# Xds100v2Emu.net
KiCad netlist of a schematic drawn in Altium Designer
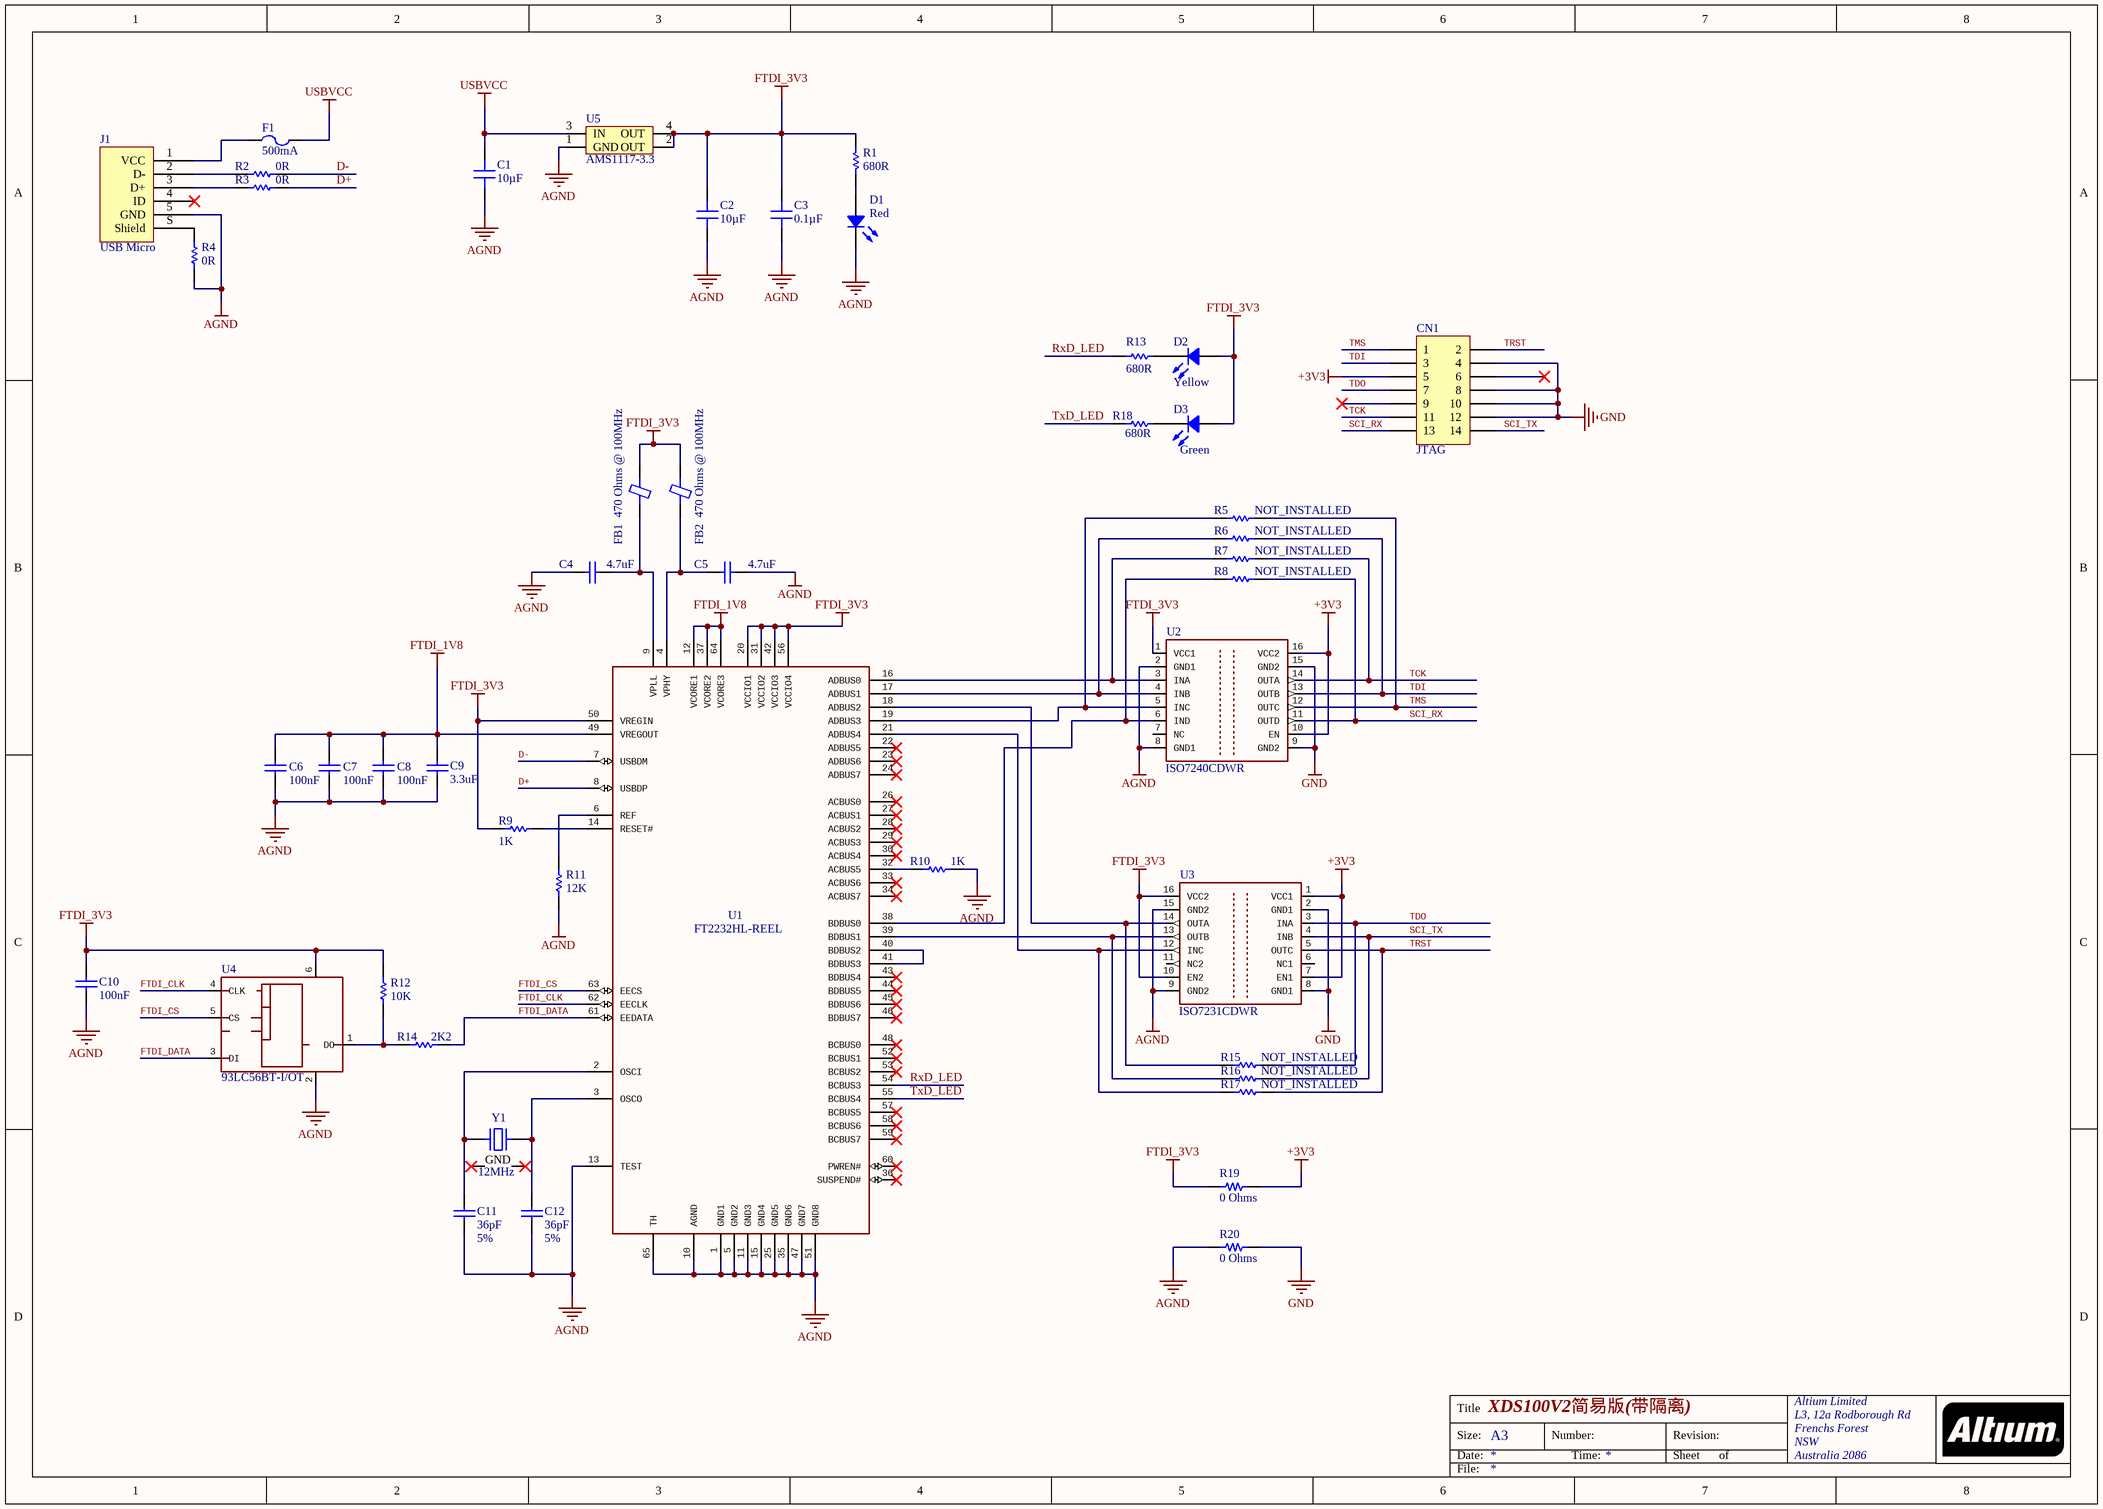
[diagram p0: Xds100v2Emu.SchDoc]

(export (version "E")
  (design (tool "Eeschema 10.0.6"))
  (components
    (comp (ref "C1")
      (value "10µF")
      (footprint "CAP 0805_2012")
      (description "CAP CER 10UF 16V X7R 0805")
      (fields
        (field (name "PART NUMBER") "CL21B106KOQNNNG")
        (field (name "MANUFACTURER") "Samsung Electro-Mechanics")
      )
      (libsource (lib "Altium Database Library V2") (part "Capacitor"))
    )
    (comp (ref "C2")
      (value "10µF")
      (footprint "CAP 0805_2012")
      (description "CAP CER 10UF 16V X7R 0805")
      (fields
        (field (name "PART NUMBER") "CL21B106KOQNNNG")
        (field (name "MANUFACTURER") "Samsung Electro-Mechanics")
      )
      (libsource (lib "Altium Database Library V2") (part "Capacitor"))
    )
    (comp (ref "C3")
      (value "0.1µF")
      (footprint "CAP 0603_1608")
      (description "CAP CER 0.1UF 16V X7R 0603")
      (fields
        (field (name "PART NUMBER") "GCJ188R71C104KA01D")
        (field (name "MANUFACTURER") "Murata Electronics")
      )
      (libsource (lib "Altium Database Library V2") (part "Capacitor"))
    )
    (comp (ref "C4")
      (value "4.7uF")
      (footprint "CAP 0603/1608")
      (description "CAP,4.7UF,+/-20%,X5R,6.3V,SMD0603")
      (fields
        (field (name "MANUFACTURER") "KEMET")
        (field (name "MANUFACTURER PART NUMBER") "C0603C475M8PACTU")
      )
      (libsource (lib "Embest") (part "C"))
    )
    (comp (ref "C5")
      (value "4.7uF")
      (footprint "CAP 0603/1608")
      (description "CAP,4.7UF,+/-20%,X5R,6.3V,SMD0603")
      (fields
        (field (name "MANUFACTURER") "KEMET")
        (field (name "MANUFACTURER PART NUMBER") "C0603C475M8PACTU")
      )
      (libsource (lib "Embest") (part "C"))
    )
    (comp (ref "C6")
      (value "100nF")
      (footprint "CAP 0603/1608")
      (description "CAP,100NF(0.1uf),+/-10%,X5R,16V,SMD0603")
      (libsource (lib "Embest") (part "C"))
    )
    (comp (ref "C7")
      (value "100nF")
      (footprint "CAP 0603/1608")
      (description "CAP,100NF(0.1uf),+/-10%,X5R,16V,SMD0603")
      (libsource (lib "Embest") (part "C"))
    )
    (comp (ref "C8")
      (value "100nF")
      (footprint "CAP 0603/1608")
      (description "CAP,100NF(0.1uf),+/-10%,X5R,16V,SMD0603")
      (libsource (lib "Embest") (part "C"))
    )
    (comp (ref "C9")
      (value "3.3uF")
      (footprint "CAP 0603/1608")
      (description "CAP,3.3uF,+/-10%,X5R,10V,SMD0603")
      (fields
        (field (name "MANUFACTURER") "MURATA")
        (field (name "MANUFACTURER PART NUMBER") "GRM188R61A335KE15D")
      )
      (libsource (lib "Embest") (part "C"))
    )
    (comp (ref "C10")
      (value "100nF")
      (footprint "CAP 0603/1608")
      (description "CAP,100NF(0.1uf),+/-10%,X5R,10V,SMD0603")
      (fields
        (field (name "MANUFACTURER") "MURATA")
        (field (name "MANUFACTURER PART NUMBER") "GRM155R61A104KA01D")
      )
      (libsource (lib "Embest") (part "C"))
    )
    (comp (ref "C11")
      (value "36pF")
      (footprint "CAP 0603/1608")
      (description "CAP,36pF,+/-5%,C0G,50V,SMD0603")
      (fields
        (field (name "RATING") "5%")
        (field (name "MANUFACTURER") "MURATA")
        (field (name "MANUFACTURER PART NUMBER") "GRM1555C1H360JA01D")
      )
      (libsource (lib "Embest") (part "C"))
    )
    (comp (ref "C12")
      (value "36pF")
      (footprint "CAP 0603/1608")
      (description "CAP,36pF,+/-5%,C0G,50V,SMD0603")
      (fields
        (field (name "RATING") "5%")
        (field (name "MANUFACTURER") "MURATA")
        (field (name "MANUFACTURER PART NUMBER") "GRM1555C1H360JA01D")
      )
      (libsource (lib "Embest") (part "C"))
    )
    (comp (ref "CN1")
      (value "JTAG")
      (footprint "JTAG调试接口")
      (description "Header, 14-Pin")
      (libsource (lib "Miscellaneous Connectors") (part "Header 7X2"))
    )
    (comp (ref "D1")
      (value "Red")
      (footprint "LED 0603_1608 RED")
      (description "LED RED CLEAR 0603 SMD")
      (fields
        (field (name "PART NUMBER") "SML-LXFM0603SIC-TR")
        (field (name "MANUFACTURER") "Lumex Opto/Components Inc.")
      )
      (libsource (lib "Altium Database Library V2") (part "LED"))
    )
    (comp (ref "D2")
      (value "Yellow")
      (footprint "LED 0603_1608 YELLOW")
      (description "LED YELLOW DIFFUSED 0603 SMD")
      (fields (field (name "PART NUMBER") "SML-D12Y8WT86") (field (name "MANUFACTURER") "Rohm Semiconductor"))
      (libsource (lib "Altium Database Library V2") (part "LED"))
    )
    (comp (ref "D3")
      (value "Green")
      (footprint "LED 0603_1608 GREEN")
      (description "LED GREEN DIFFUSED 0603 SMD")
      (fields (field (name "PART NUMBER") "SML-D13FWT86") (field (name "MANUFACTURER") "Rohm Semiconductor"))
      (libsource (lib "Altium Database Library V2") (part "LED"))
    )
    (comp (ref "F1")
      (value "500mA")
      (footprint "FUSM4632X85N")
      (description "PTC RESETTABLE .50A 15V 1812")
      (fields (field (name "MANUFACTURER") "BOURNS") (field (name "MANUFACTURER PART NUMBER") "MF-MSMF050-2"))
      (libsource (lib "Embest") (part "F"))
    )
    (comp (ref "FB1")
      (value "470 Ohms @ 100MHz")
      (footprint "FER 0603_1608")
      (description "FERRITE BEAD 470 OHM 0603 1LN")
      (fields
        (field (name "PART NUMBER") "BLM18BB471SN1D")
        (field (name "MANUFACTURER") "Murata Electronics")
      )
      (libsource (lib "Altium Database Library V2") (part "Ferrite Chip"))
    )
    (comp (ref "FB2")
      (value "470 Ohms @ 100MHz")
      (footprint "FER 0603_1608")
      (description "FERRITE BEAD 470 OHM 0603 1LN")
      (fields
        (field (name "PART NUMBER") "BLM18BB471SN1D")
        (field (name "MANUFACTURER") "Murata Electronics")
      )
      (libsource (lib "Altium Database Library V2") (part "Ferrite Chip"))
    )
    (comp (ref "J1")
      (value "USB Micro")
      (footprint "FCI USB 10118193-0001LF")
      (libsource (lib "Connectors") (part "USB 2.0 Type B Micro"))
    )
    (comp (ref "R1")
      (value "680R")
      (footprint "RES 0603/1608")
      (description "RES,680R,+/-5%,1/10W,SMD0603")
      (libsource (lib "Embest") (part "R"))
    )
    (comp (ref "R2")
      (value "0R")
      (footprint "RES 0603/1608")
      (description "RES,0R,+/-5%,1/10W,SMD0603")
      (libsource (lib "Embest") (part "R"))
    )
    (comp (ref "R3")
      (value "0R")
      (footprint "RES 0603/1608")
      (description "RES,0R,+/-5%,1/10W,SMD0603")
      (libsource (lib "Embest") (part "R"))
    )
    (comp (ref "R4")
      (value "0R")
      (footprint "RES 0603/1608")
      (description "RES,0R,+/-5%,1/10W,SMD0603")
      (libsource (lib "Embest") (part "R"))
    )
    (comp (ref "R5")
      (value "NOT_INSTALLED")
      (footprint "RES 0603/1608")
      (description "RES,0R,+/-5%,1/10W,SMD0603")
      (libsource (lib "Embest") (part "R"))
    )
    (comp (ref "R6")
      (value "NOT_INSTALLED")
      (footprint "RES 0603/1608")
      (description "RES,0R,+/-5%,1/10W,SMD0603")
      (libsource (lib "Embest") (part "R"))
    )
    (comp (ref "R7")
      (value "NOT_INSTALLED")
      (footprint "RES 0603/1608")
      (description "RES,0R,+/-5%,1/10W,SMD0603")
      (libsource (lib "Embest") (part "R"))
    )
    (comp (ref "R8")
      (value "NOT_INSTALLED")
      (footprint "RES 0603/1608")
      (description "RES,0R,+/-5%,1/10W,SMD0603")
      (libsource (lib "Embest") (part "R"))
    )
    (comp (ref "R9")
      (value "1K")
      (footprint "RES 0603/1608")
      (description "RES,1K,+/-5%,1/10W,SMD0603")
      (libsource (lib "Embest") (part "R"))
    )
    (comp (ref "R10")
      (value "1K")
      (footprint "RES 0603/1608")
      (description "RES,1K,+/-1%,1/10W,SMD0603")
      (libsource (lib "Embest") (part "R"))
    )
    (comp (ref "R11")
      (value "12K")
      (footprint "RES 0603/1608")
      (description "RES,12K,+/-1%,1/10W,SMD0603")
      (libsource (lib "Embest") (part "R"))
    )
    (comp (ref "R12")
      (value "10K")
      (footprint "RES 0603/1608")
      (description "RES,10K,+/-1%,1/10W,SMD0603")
      (libsource (lib "Embest") (part "R"))
    )
    (comp (ref "R13")
      (value "680R")
      (footprint "RES 0603/1608")
      (description "RES,680R,+/-5%,1/10W,SMD0603")
      (libsource (lib "Embest") (part "R"))
    )
    (comp (ref "R14")
      (value "2K2")
      (footprint "RES 0603/1608")
      (description "RES,2K2,+/-1%,1/10W,SMD0603")
      (libsource (lib "Embest") (part "R"))
    )
    (comp (ref "R15")
      (value "NOT_INSTALLED")
      (footprint "RES 0603/1608")
      (description "RES,0R,+/-5%,1/10W,SMD0603")
      (libsource (lib "Embest") (part "R"))
    )
    (comp (ref "R16")
      (value "NOT_INSTALLED")
      (footprint "RES 0603/1608")
      (description "RES,0R,+/-5%,1/10W,SMD0603")
      (libsource (lib "Embest") (part "R"))
    )
    (comp (ref "R17")
      (value "NOT_INSTALLED")
      (footprint "RES 0603/1608")
      (description "RES,0R,+/-5%,1/10W,SMD0603")
      (libsource (lib "Embest") (part "R"))
    )
    (comp (ref "R18")
      (value "680R")
      (footprint "RES 0603/1608")
      (description "RES,680R,+/-1%,1/10W,SMD0603")
      (libsource (lib "Embest") (part "R"))
    )
    (comp (ref "R19")
      (value "0 Ohms")
      (footprint "RES 0603_1608")
      (description "RES 0 OHM JUMPER 1/10W 0603")
      (fields (field (name "PART NUMBER") "SFR03EZPJ000") (field (name "MANUFACTURER") "Rohm Semiconductor"))
      (libsource (lib "Altium Database Library V2") (part "Resistor"))
    )
    (comp (ref "R20")
      (value "0 Ohms")
      (footprint "RES 0603_1608")
      (description "RES 0 OHM JUMPER 1/10W 0603")
      (fields (field (name "PART NUMBER") "SFR03EZPJ000") (field (name "MANUFACTURER") "Rohm Semiconductor"))
      (libsource (lib "Altium Database Library V2") (part "Resistor"))
    )
    (comp (ref "U1")
      (value "FT2232HL-REEL")
      (footprint "LQFP64_N")
      (description "IC,Dual High Speed USB to Multipurpose UART/FIFO IC,FT2232HL-REEL,LQFP-64,SMD")
      (fields (field (name "MANUFACTURER") "FTDI") (field (name "Comment") "FT2232HQ-REEL"))
      (libsource (lib "Embest") (part "FT2232HQ"))
    )
    (comp (ref "U2")
      (value "ISO7240CDWR")
      (footprint "SOIC127P1030X265-16N")
      (description "IC DGTL ISO 4CH CMOS 16SOIC,CUSTOMER SUPPLY")
      (fields (field (name "MANUFACTURER") "TI"))
      (libsource (lib "Embest") (part "ISO7240"))
    )
    (comp (ref "U3")
      (value "ISO7231CDWR")
      (footprint "SOIC127P1030X265-16N")
      (description "IC DGTL ISO 3CH CMOS 16SOIC,CUSTOMER SUPPLY")
      (fields (field (name "MANUFACTURER") "TI"))
      (libsource (lib "Embest") (part "ISO7231"))
    )
    (comp (ref "U4")
      (value "93LC56BT-I/OT")
      (footprint "SOT23-6")
      (description "IC,EEPROM Serial-Microwire 2K-Bit 128 x 16 2MHz,93LC56BT-I/OT,SOT-23-6,SMD")
      (fields (field (name "MANUFACTURER") "MICROCHIP"))
      (libsource (lib "Embest") (part "93LC56BT"))
    )
    (comp (ref "U5")
      (value "AMS1117-3.3")
      (footprint "PCB - LEADED - SOT - DIODES SOT-223:DIODES SOT-223")
      (description "电源转换5Vto3.3V")
      (libsource (lib "IC") (part "AMS1117"))
    )
    (comp (ref "Y1")
      (value "12MHz")
      (footprint "NDK NX3225SA")
      (description "CRYSTAL 12.0000MHZ 8PF SMD")
      (fields
        (field (name "PART NUMBER") "NX3225SA-12MHZ-STD-CSR-6")
        (field (name "MANUFACTURER") "NDK America, Inc.")
      )
      (libsource (lib "Altium Database Library V2") (part "NDK Crystal NX3225SA"))
    )
  )
  (nets
    (net (code "1") (name "+3V3") (class "Default")
      (node (ref "CN1") (pin "5") (pinfunction "5_5") (pintype "passive"))
      (node (ref "R19") (pin "2") (pinfunction "2_2") (pintype "passive"))
      (node (ref "U2") (pin "10") (pinfunction "EN_10") (pintype "passive"))
      (node (ref "U2") (pin "16") (pinfunction "VCC2_16") (pintype "power_in"))
      (node (ref "U3") (pin "1") (pinfunction "VCC1_1") (pintype "power_in"))
      (node (ref "U3") (pin "7") (pinfunction "EN1_7") (pintype "passive"))
    )
    (net (code "2") (name "/D+") (class "Default")
      (node (ref "R3") (pin "2") (pinfunction "2_2") (pintype "passive"))
      (node (ref "U1") (pin "8") (pinfunction "USBDP_8") (pintype "bidirectional"))
    )
    (net (code "3") (name "/D-") (class "Default")
      (node (ref "R2") (pin "2") (pinfunction "2_2") (pintype "passive"))
      (node (ref "U1") (pin "7") (pinfunction "USBDM_7") (pintype "bidirectional"))
    )
    (net (code "4") (name "/FTDI_CLK") (class "Default")
      (node (ref "U1") (pin "62") (pinfunction "EECLK_62") (pintype "bidirectional"))
      (node (ref "U4") (pin "4") (pinfunction "CLK_4") (pintype "passive"))
    )
    (net (code "5") (name "/FTDI_CS") (class "Default")
      (node (ref "U1") (pin "63") (pinfunction "EECS_63") (pintype "bidirectional"))
      (node (ref "U4") (pin "5") (pinfunction "CS_5") (pintype "passive"))
    )
    (net (code "6") (name "/FTDI_DATA") (class "Default")
      (node (ref "R14") (pin "2") (pinfunction "2_2") (pintype "passive"))
      (node (ref "U1") (pin "61") (pinfunction "EEDATA_61") (pintype "bidirectional"))
      (node (ref "U4") (pin "3") (pinfunction "DI_3") (pintype "passive"))
    )
    (net (code "7") (name "/RxD_LED") (class "Default")
      (node (ref "R13") (pin "1") (pinfunction "1_1") (pintype "passive"))
      (node (ref "U1") (pin "54") (pinfunction "BCBUS3_54") (pintype "passive"))
    )
    (net (code "8") (name "/SCI_RX") (class "Default")
      (node (ref "CN1") (pin "13") (pinfunction "13_13") (pintype "passive"))
      (node (ref "R8") (pin "2") (pinfunction "2_2") (pintype "passive"))
      (node (ref "U2") (pin "11") (pinfunction "OUTD_11") (pintype "output"))
    )
    (net (code "9") (name "/SCI_TX") (class "Default")
      (node (ref "CN1") (pin "14") (pinfunction "14_14") (pintype "passive"))
      (node (ref "R16") (pin "2") (pinfunction "2_2") (pintype "passive"))
      (node (ref "U3") (pin "4") (pinfunction "INB_4") (pintype "passive"))
    )
    (net (code "10") (name "/TCK") (class "Default")
      (node (ref "CN1") (pin "11") (pinfunction "11_11") (pintype "passive"))
      (node (ref "R7") (pin "2") (pinfunction "2_2") (pintype "passive"))
      (node (ref "U2") (pin "14") (pinfunction "OUTA_14") (pintype "output"))
    )
    (net (code "11") (name "/TDI") (class "Default")
      (node (ref "CN1") (pin "3") (pinfunction "3_3") (pintype "passive"))
      (node (ref "R6") (pin "2") (pinfunction "2_2") (pintype "passive"))
      (node (ref "U2") (pin "13") (pinfunction "OUTB_13") (pintype "output"))
    )
    (net (code "12") (name "/TDO") (class "Default")
      (node (ref "CN1") (pin "7") (pinfunction "7_7") (pintype "passive"))
      (node (ref "R15") (pin "2") (pinfunction "2_2") (pintype "passive"))
      (node (ref "U3") (pin "3") (pinfunction "INA_3") (pintype "passive"))
    )
    (net (code "13") (name "/TMS") (class "Default")
      (node (ref "CN1") (pin "1") (pinfunction "1_1") (pintype "passive"))
      (node (ref "R5") (pin "2") (pinfunction "2_2") (pintype "passive"))
      (node (ref "U2") (pin "12") (pinfunction "OUTC_12") (pintype "output"))
    )
    (net (code "14") (name "/TRST") (class "Default")
      (node (ref "CN1") (pin "2") (pinfunction "2_2") (pintype "passive"))
      (node (ref "R17") (pin "2") (pinfunction "2_2") (pintype "passive"))
      (node (ref "U3") (pin "5") (pinfunction "OUTC_5") (pintype "passive"))
    )
    (net (code "15") (name "/TxD_LED") (class "Default")
      (node (ref "R18") (pin "1") (pinfunction "1_1") (pintype "passive"))
      (node (ref "U1") (pin "55") (pinfunction "BCBUS4_55") (pintype "passive"))
    )
    (net (code "16") (name "AGND") (class "Default")
      (node (ref "C1") (pin "1") (pinfunction "1_1") (pintype "passive"))
      (node (ref "C10") (pin "1") (pinfunction "1_1") (pintype "passive"))
      (node (ref "C11") (pin "1") (pinfunction "1_1") (pintype "passive"))
      (node (ref "C12") (pin "1") (pinfunction "1_1") (pintype "passive"))
      (node (ref "C2") (pin "1") (pinfunction "1_1") (pintype "passive"))
      (node (ref "C3") (pin "1") (pinfunction "1_1") (pintype "passive"))
      (node (ref "C4") (pin "1") (pinfunction "1_1") (pintype "passive"))
      (node (ref "C5") (pin "2") (pinfunction "2_2") (pintype "passive"))
      (node (ref "C6") (pin "1") (pinfunction "1_1") (pintype "passive"))
      (node (ref "C7") (pin "1") (pinfunction "1_1") (pintype "passive"))
      (node (ref "C8") (pin "1") (pinfunction "1_1") (pintype "passive"))
      (node (ref "C9") (pin "1") (pinfunction "1_1") (pintype "passive"))
      (node (ref "D1") (pin "2") (pinfunction "2_2") (pintype "passive"))
      (node (ref "J1") (pin "5") (pinfunction "GND_5") (pintype "passive"))
      (node (ref "R10") (pin "2") (pinfunction "2_2") (pintype "passive"))
      (node (ref "R11") (pin "1") (pinfunction "1_1") (pintype "passive"))
      (node (ref "R20") (pin "1") (pinfunction "1_1") (pintype "passive"))
      (node (ref "R4") (pin "1") (pinfunction "1_1") (pintype "passive"))
      (node (ref "U1") (pin "1") (pinfunction "GND1_1") (pintype "power_in"))
      (node (ref "U1") (pin "10") (pinfunction "AGND_10") (pintype "power_in"))
      (node (ref "U1") (pin "11") (pinfunction "GND3_11") (pintype "power_in"))
      (node (ref "U1") (pin "13") (pinfunction "TEST_13") (pintype "power_in"))
      (node (ref "U1") (pin "15") (pinfunction "GND4_15") (pintype "power_in"))
      (node (ref "U1") (pin "25") (pinfunction "GND5_25") (pintype "power_in"))
      (node (ref "U1") (pin "35") (pinfunction "GND6_35") (pintype "power_in"))
      (node (ref "U1") (pin "47") (pinfunction "GND7_47") (pintype "power_in"))
      (node (ref "U1") (pin "5") (pinfunction "GND2_5") (pintype "power_in"))
      (node (ref "U1") (pin "51") (pinfunction "GND8_51") (pintype "power_in"))
      (node (ref "U1") (pin "65") (pinfunction "TH_65") (pintype "power_in"))
      (node (ref "U2") (pin "2") (pinfunction "GND1_2") (pintype "power_in"))
      (node (ref "U2") (pin "8") (pinfunction "GND1_8") (pintype "power_in"))
      (node (ref "U3") (pin "15") (pinfunction "GND2_15") (pintype "power_in"))
      (node (ref "U3") (pin "9") (pinfunction "GND2_9") (pintype "power_in"))
      (node (ref "U4") (pin "2") (pinfunction "GND_2") (pintype "power_in"))
      (node (ref "U5") (pin "1") (pinfunction "GND_1") (pintype "passive"))
    )
    (net (code "17") (name "FTDI_1V8") (class "Default")
      (node (ref "C6") (pin "2") (pinfunction "2_2") (pintype "passive"))
      (node (ref "C7") (pin "2") (pinfunction "2_2") (pintype "passive"))
      (node (ref "C8") (pin "2") (pinfunction "2_2") (pintype "passive"))
      (node (ref "C9") (pin "2") (pinfunction "2_2") (pintype "passive"))
      (node (ref "U1") (pin "12") (pinfunction "VCORE1_12") (pintype "power_in"))
      (node (ref "U1") (pin "37") (pinfunction "VCORE2_37") (pintype "power_in"))
      (node (ref "U1") (pin "49") (pinfunction "VREGOUT_49") (pintype "power_in"))
      (node (ref "U1") (pin "64") (pinfunction "VCORE3_64") (pintype "power_in"))
    )
    (net (code "18") (name "FTDI_3V3") (class "Default")
      (node (ref "C10") (pin "2") (pinfunction "2_2") (pintype "passive"))
      (node (ref "C2") (pin "2") (pinfunction "2_2") (pintype "passive"))
      (node (ref "C3") (pin "2") (pinfunction "2_2") (pintype "passive"))
      (node (ref "D2") (pin "1") (pinfunction "1_1") (pintype "passive"))
      (node (ref "D3") (pin "1") (pinfunction "1_1") (pintype "passive"))
      (node (ref "FB1") (pin "2") (pinfunction "2_2") (pintype "passive"))
      (node (ref "FB2") (pin "2") (pinfunction "2_2") (pintype "passive"))
      (node (ref "R1") (pin "2") (pinfunction "2_2") (pintype "passive"))
      (node (ref "R12") (pin "1") (pinfunction "1_1") (pintype "passive"))
      (node (ref "R19") (pin "1") (pinfunction "1_1") (pintype "passive"))
      (node (ref "R9") (pin "1") (pinfunction "1_1") (pintype "passive"))
      (node (ref "U1") (pin "20") (pinfunction "VCCIO1_20") (pintype "power_in"))
      (node (ref "U1") (pin "31") (pinfunction "VCCIO2_31") (pintype "power_in"))
      (node (ref "U1") (pin "42") (pinfunction "VCCIO3_42") (pintype "power_in"))
      (node (ref "U1") (pin "50") (pinfunction "VREGIN_50") (pintype "power_in"))
      (node (ref "U1") (pin "56") (pinfunction "VCCIO4_56") (pintype "power_in"))
      (node (ref "U2") (pin "1") (pinfunction "VCC1_1") (pintype "power_in"))
      (node (ref "U3") (pin "10") (pinfunction "EN2_10") (pintype "passive"))
      (node (ref "U3") (pin "16") (pinfunction "VCC2_16") (pintype "power_in"))
      (node (ref "U4") (pin "6") (pinfunction "VCC_6") (pintype "power_in"))
      (node (ref "U5") (pin "2") (pinfunction "OUT_2") (pintype "passive"))
      (node (ref "U5") (pin "4") (pinfunction "OUT_4") (pintype "passive"))
    )
    (net (code "19") (name "GND") (class "Default")
      (node (ref "CN1") (pin "10") (pinfunction "10_10") (pintype "passive"))
      (node (ref "CN1") (pin "12") (pinfunction "12_12") (pintype "passive"))
      (node (ref "CN1") (pin "4") (pinfunction "4_4") (pintype "passive"))
      (node (ref "CN1") (pin "8") (pinfunction "8_8") (pintype "passive"))
      (node (ref "R20") (pin "2") (pinfunction "2_2") (pintype "passive"))
      (node (ref "U2") (pin "15") (pinfunction "GND2_15") (pintype "power_in"))
      (node (ref "U2") (pin "9") (pinfunction "GND2_9") (pintype "power_in"))
      (node (ref "U3") (pin "2") (pinfunction "GND1_2") (pintype "power_in"))
      (node (ref "U3") (pin "8") (pinfunction "GND1_8") (pintype "power_in"))
    )
    (net (code "20") (name "Net-(D1-Pad1)") (class "Default")
      (node (ref "D1") (pin "1") (pinfunction "1_1") (pintype "passive"))
      (node (ref "R1") (pin "1") (pinfunction "1_1") (pintype "passive"))
    )
    (net (code "21") (name "Net-(D2-Pad2)") (class "Default")
      (node (ref "D2") (pin "2") (pinfunction "2_2") (pintype "passive"))
      (node (ref "R13") (pin "2") (pinfunction "2_2") (pintype "passive"))
    )
    (net (code "22") (name "Net-(D3-Pad2)") (class "Default")
      (node (ref "D3") (pin "2") (pinfunction "2_2") (pintype "passive"))
      (node (ref "R18") (pin "2") (pinfunction "2_2") (pintype "passive"))
    )
    (net (code "23") (name "Net-(J1-D+)") (class "Default")
      (node (ref "J1") (pin "3") (pinfunction "D+_3") (pintype "passive"))
      (node (ref "R3") (pin "1") (pinfunction "1_1") (pintype "passive"))
    )
    (net (code "24") (name "Net-(J1-D-)") (class "Default")
      (node (ref "J1") (pin "2") (pinfunction "D-_2") (pintype "passive"))
      (node (ref "R2") (pin "1") (pinfunction "1_1") (pintype "passive"))
    )
    (net (code "25") (name "Net-(J1-Shield)") (class "Default")
      (node (ref "J1") (pin "S") (pinfunction "Shield_S") (pintype "passive"))
      (node (ref "R4") (pin "2") (pinfunction "2_2") (pintype "passive"))
    )
    (net (code "26") (name "Net-(J1-VCC)") (class "Default")
      (node (ref "F1") (pin "1") (pinfunction "1_1") (pintype "passive"))
      (node (ref "J1") (pin "1") (pinfunction "VCC_1") (pintype "passive"))
    )
    (net (code "27") (name "Net-(U1-ACBUS5)") (class "Default")
      (node (ref "R10") (pin "1") (pinfunction "1_1") (pintype "passive"))
      (node (ref "U1") (pin "32") (pinfunction "ACBUS5_32") (pintype "passive"))
    )
    (net (code "28") (name "Net-(U1-ADBUS0)") (class "Default")
      (node (ref "R7") (pin "1") (pinfunction "1_1") (pintype "passive"))
      (node (ref "U1") (pin "16") (pinfunction "ADBUS0_16") (pintype "passive"))
      (node (ref "U2") (pin "3") (pinfunction "INA_3") (pintype "passive"))
    )
    (net (code "29") (name "Net-(U1-ADBUS1)") (class "Default")
      (node (ref "R6") (pin "1") (pinfunction "1_1") (pintype "passive"))
      (node (ref "U1") (pin "17") (pinfunction "ADBUS1_17") (pintype "passive"))
      (node (ref "U2") (pin "4") (pinfunction "INB_4") (pintype "passive"))
    )
    (net (code "30") (name "Net-(U1-ADBUS2)") (class "Default")
      (node (ref "R15") (pin "1") (pinfunction "1_1") (pintype "passive"))
      (node (ref "U1") (pin "18") (pinfunction "ADBUS2_18") (pintype "passive"))
      (node (ref "U3") (pin "14") (pinfunction "OUTA_14") (pintype "output"))
    )
    (net (code "31") (name "Net-(U1-ADBUS3)") (class "Default")
      (node (ref "R5") (pin "1") (pinfunction "1_1") (pintype "passive"))
      (node (ref "U1") (pin "19") (pinfunction "ADBUS3_19") (pintype "passive"))
      (node (ref "U2") (pin "5") (pinfunction "INC_5") (pintype "passive"))
    )
    (net (code "32") (name "Net-(U1-ADBUS4)") (class "Default")
      (node (ref "R17") (pin "1") (pinfunction "1_1") (pintype "passive"))
      (node (ref "U1") (pin "21") (pinfunction "ADBUS4_21") (pintype "passive"))
      (node (ref "U3") (pin "12") (pinfunction "INC_12") (pintype "output"))
    )
    (net (code "33") (name "Net-(U1-BDBUS0)") (class "Default")
      (node (ref "R8") (pin "1") (pinfunction "1_1") (pintype "passive"))
      (node (ref "U1") (pin "38") (pinfunction "BDBUS0_38") (pintype "passive"))
      (node (ref "U2") (pin "6") (pinfunction "IND_6") (pintype "passive"))
    )
    (net (code "34") (name "Net-(U1-BDBUS1)") (class "Default")
      (node (ref "R16") (pin "1") (pinfunction "1_1") (pintype "passive"))
      (node (ref "U1") (pin "39") (pinfunction "BDBUS1_39") (pintype "passive"))
      (node (ref "U3") (pin "13") (pinfunction "OUTB_13") (pintype "output"))
    )
    (net (code "35") (name "Net-(U1-BDBUS2)") (class "Default")
      (node (ref "U1") (pin "40") (pinfunction "BDBUS2_40") (pintype "passive"))
      (node (ref "U1") (pin "41") (pinfunction "BDBUS3_41") (pintype "passive"))
    )
    (net (code "36") (name "Net-(U1-OSCI)") (class "Default")
      (node (ref "C11") (pin "2") (pinfunction "2_2") (pintype "passive"))
      (node (ref "U1") (pin "2") (pinfunction "OSCI_2") (pintype "passive"))
      (node (ref "Y1") (pin "1") (pinfunction "1_1") (pintype "passive"))
    )
    (net (code "37") (name "Net-(U1-OSCO)") (class "Default")
      (node (ref "C12") (pin "2") (pinfunction "2_2") (pintype "passive"))
      (node (ref "U1") (pin "3") (pinfunction "OSCO_3") (pintype "passive"))
      (node (ref "Y1") (pin "3") (pinfunction "3_3") (pintype "passive"))
    )
    (net (code "38") (name "Net-(U1-REF)") (class "Default")
      (node (ref "R11") (pin "2") (pinfunction "2_2") (pintype "passive"))
      (node (ref "U1") (pin "6") (pinfunction "REF_6") (pintype "passive"))
    )
    (net (code "39") (name "Net-(U1-RESET#)") (class "Default")
      (node (ref "R9") (pin "2") (pinfunction "2_2") (pintype "passive"))
      (node (ref "U1") (pin "14") (pinfunction "RESET#_14") (pintype "passive"))
    )
    (net (code "40") (name "Net-(U1-VPHY)") (class "Default")
      (node (ref "C5") (pin "1") (pinfunction "1_1") (pintype "passive"))
      (node (ref "FB2") (pin "1") (pinfunction "1_1") (pintype "passive"))
      (node (ref "U1") (pin "4") (pinfunction "VPHY_4") (pintype "passive"))
    )
    (net (code "41") (name "Net-(U1-VPLL)") (class "Default")
      (node (ref "C4") (pin "2") (pinfunction "2_2") (pintype "passive"))
      (node (ref "FB1") (pin "1") (pinfunction "1_1") (pintype "passive"))
      (node (ref "U1") (pin "9") (pinfunction "VPLL_9") (pintype "passive"))
    )
    (net (code "42") (name "Net-(U4-DO)") (class "Default")
      (node (ref "R12") (pin "2") (pinfunction "2_2") (pintype "passive"))
      (node (ref "R14") (pin "1") (pinfunction "1_1") (pintype "passive"))
      (node (ref "U4") (pin "1") (pinfunction "DO_1") (pintype "tri_state"))
    )
    (net (code "43") (name "USBVCC") (class "Default")
      (node (ref "C1") (pin "2") (pinfunction "2_2") (pintype "passive"))
      (node (ref "F1") (pin "2") (pinfunction "2_2") (pintype "passive"))
      (node (ref "U5") (pin "3") (pinfunction "IN_3") (pintype "passive"))
    )
    (net (code "44") (name "unconnected-(CN1-Pad6)") (class "Default")
      (node (ref "CN1") (pin "6") (pinfunction "6_6") (pintype "passive+no_connect"))
    )
    (net (code "45") (name "unconnected-(CN1-Pad9)") (class "Default")
      (node (ref "CN1") (pin "9") (pinfunction "9_9") (pintype "passive+no_connect"))
    )
    (net (code "46") (name "unconnected-(J1-ID-Pad4)") (class "Default")
      (node (ref "J1") (pin "4") (pinfunction "ID_4") (pintype "passive+no_connect"))
    )
    (net (code "47") (name "unconnected-(U1-ACBUS0-Pad26)") (class "Default")
      (node (ref "U1") (pin "26") (pinfunction "ACBUS0_26") (pintype "passive+no_connect"))
    )
    (net (code "48") (name "unconnected-(U1-ACBUS1-Pad27)") (class "Default")
      (node (ref "U1") (pin "27") (pinfunction "ACBUS1_27") (pintype "passive+no_connect"))
    )
    (net (code "49") (name "unconnected-(U1-ACBUS2-Pad28)") (class "Default")
      (node (ref "U1") (pin "28") (pinfunction "ACBUS2_28") (pintype "passive+no_connect"))
    )
    (net (code "50") (name "unconnected-(U1-ACBUS3-Pad29)") (class "Default")
      (node (ref "U1") (pin "29") (pinfunction "ACBUS3_29") (pintype "passive+no_connect"))
    )
    (net (code "51") (name "unconnected-(U1-ACBUS4-Pad30)") (class "Default")
      (node (ref "U1") (pin "30") (pinfunction "ACBUS4_30") (pintype "passive+no_connect"))
    )
    (net (code "52") (name "unconnected-(U1-ACBUS6-Pad33)") (class "Default")
      (node (ref "U1") (pin "33") (pinfunction "ACBUS6_33") (pintype "passive+no_connect"))
    )
    (net (code "53") (name "unconnected-(U1-ACBUS7-Pad34)") (class "Default")
      (node (ref "U1") (pin "34") (pinfunction "ACBUS7_34") (pintype "passive+no_connect"))
    )
    (net (code "54") (name "unconnected-(U1-ADBUS5-Pad22)") (class "Default")
      (node (ref "U1") (pin "22") (pinfunction "ADBUS5_22") (pintype "passive+no_connect"))
    )
    (net (code "55") (name "unconnected-(U1-ADBUS6-Pad23)") (class "Default")
      (node (ref "U1") (pin "23") (pinfunction "ADBUS6_23") (pintype "passive+no_connect"))
    )
    (net (code "56") (name "unconnected-(U1-ADBUS7-Pad24)") (class "Default")
      (node (ref "U1") (pin "24") (pinfunction "ADBUS7_24") (pintype "passive+no_connect"))
    )
    (net (code "57") (name "unconnected-(U1-BCBUS0-Pad48)") (class "Default")
      (node (ref "U1") (pin "48") (pinfunction "BCBUS0_48") (pintype "passive+no_connect"))
    )
    (net (code "58") (name "unconnected-(U1-BCBUS1-Pad52)") (class "Default")
      (node (ref "U1") (pin "52") (pinfunction "BCBUS1_52") (pintype "passive+no_connect"))
    )
    (net (code "59") (name "unconnected-(U1-BCBUS2-Pad53)") (class "Default")
      (node (ref "U1") (pin "53") (pinfunction "BCBUS2_53") (pintype "passive+no_connect"))
    )
    (net (code "60") (name "unconnected-(U1-BCBUS5-Pad57)") (class "Default")
      (node (ref "U1") (pin "57") (pinfunction "BCBUS5_57") (pintype "passive+no_connect"))
    )
    (net (code "61") (name "unconnected-(U1-BCBUS6-Pad58)") (class "Default")
      (node (ref "U1") (pin "58") (pinfunction "BCBUS6_58") (pintype "passive+no_connect"))
    )
    (net (code "62") (name "unconnected-(U1-BCBUS7-Pad59)") (class "Default")
      (node (ref "U1") (pin "59") (pinfunction "BCBUS7_59") (pintype "passive+no_connect"))
    )
    (net (code "63") (name "unconnected-(U1-BDBUS4-Pad43)") (class "Default")
      (node (ref "U1") (pin "43") (pinfunction "BDBUS4_43") (pintype "passive+no_connect"))
    )
    (net (code "64") (name "unconnected-(U1-BDBUS5-Pad44)") (class "Default")
      (node (ref "U1") (pin "44") (pinfunction "BDBUS5_44") (pintype "passive+no_connect"))
    )
    (net (code "65") (name "unconnected-(U1-BDBUS6-Pad45)") (class "Default")
      (node (ref "U1") (pin "45") (pinfunction "BDBUS6_45") (pintype "passive+no_connect"))
    )
    (net (code "66") (name "unconnected-(U1-BDBUS7-Pad46)") (class "Default")
      (node (ref "U1") (pin "46") (pinfunction "BDBUS7_46") (pintype "passive+no_connect"))
    )
    (net (code "67") (name "unconnected-(U1-PWREN#-Pad60)") (class "Default")
      (node (ref "U1") (pin "60") (pinfunction "PWREN#_60") (pintype "bidirectional+no_connect"))
    )
    (net (code "68") (name "unconnected-(U1-SUSPEND#-Pad36)") (class "Default")
      (node (ref "U1") (pin "36") (pinfunction "SUSPEND#_36") (pintype "bidirectional+no_connect"))
    )
    (net (code "69") (name "unconnected-(U2-NC-Pad7)") (class "Default")
      (node (ref "U2") (pin "7") (pinfunction "NC_7") (pintype "passive"))
    )
    (net (code "70") (name "unconnected-(U3-NC1-Pad6)") (class "Default")
      (node (ref "U3") (pin "6") (pinfunction "NC1_6") (pintype "passive"))
    )
    (net (code "71") (name "unconnected-(U3-NC2-Pad11)") (class "Default")
      (node (ref "U3") (pin "11") (pinfunction "NC2_11") (pintype "output"))
    )
    (net (code "72") (name "unconnected-(Y1-GND-Pad2)") (class "Default")
      (node (ref "Y1") (pin "2") (pinfunction "GND_2") (pintype "passive+no_connect"))
    )
    (net (code "73") (name "unconnected-(Y1-GND-Pad4)") (class "Default")
      (node (ref "Y1") (pin "4") (pinfunction "GND_4") (pintype "passive+no_connect"))
    )
  )
)
